# senzMate_ecandMoisture_design_cycle2.net
KiCad netlist of a schematic drawn in Altium Designer
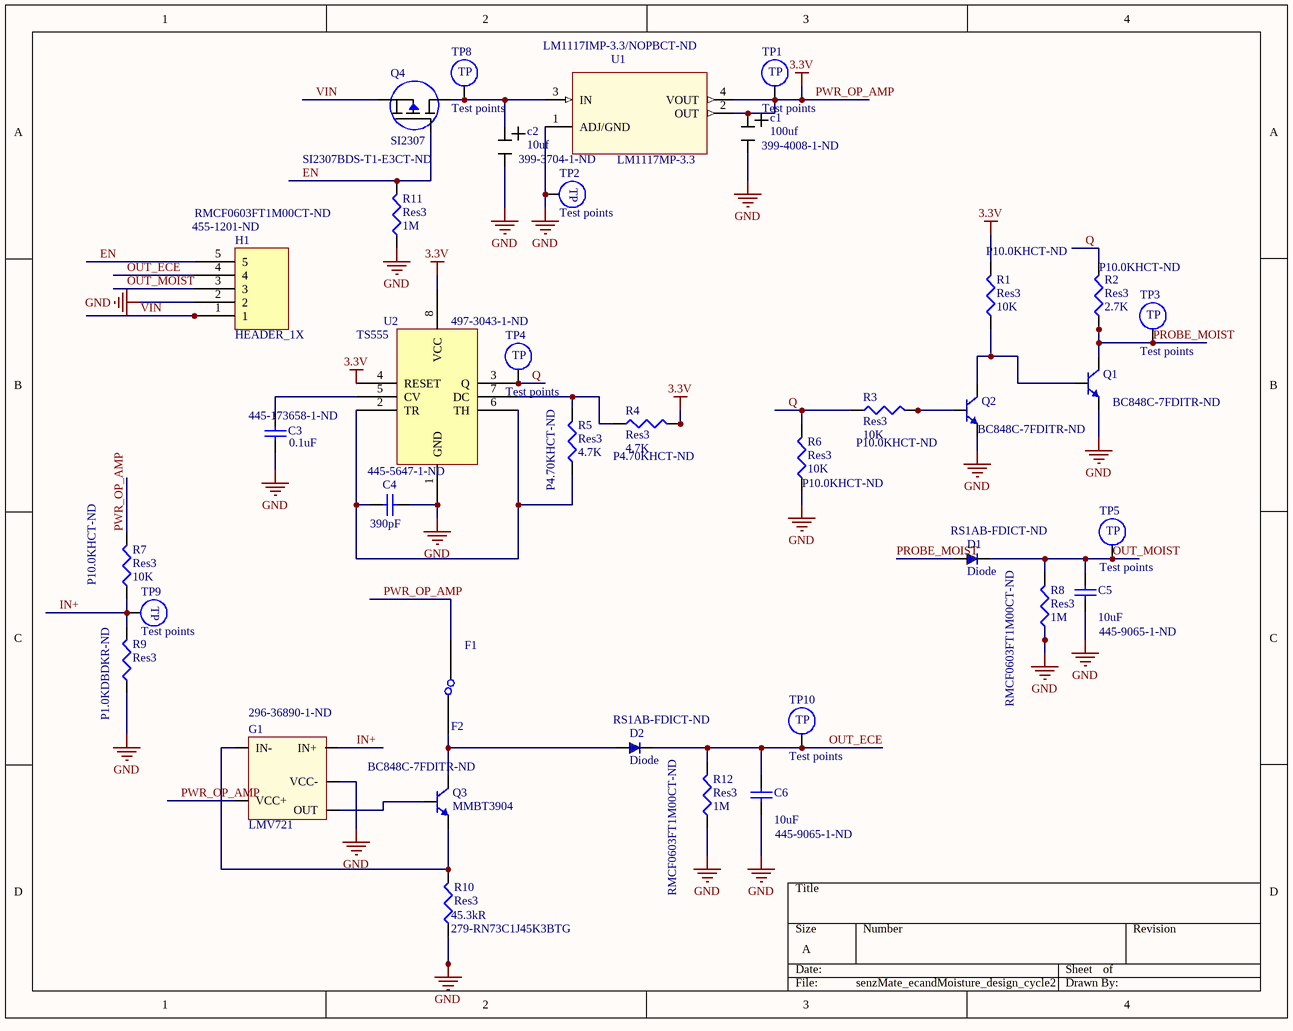
[diagram p0: senzMate_ecandMoisture_design_cycle2.SchDoc]

(export (version "E")
  (design (tool "Eeschema 10.0.6"))
  (components
    (comp (ref "c1")
      (value "100uf")
      (footprint "tan_cap")
      (description "Tantalum Surface Mount Capacitors – Standard Tantalum")
      (fields
        (field (name "SUPPLIER PART NUMBER 1") "399-4008-1-ND")
        (field (name "MANUFACTURER") "KEMET")
        (field (name "MANUFACTURER PART NUMBER") "T520B107M006ATE040")
      )
      (libsource (lib "Misc1") (part "tant_cap"))
    )
    (comp (ref "c2")
      (value "10uf")
      (footprint "tan_cap")
      (description "Tantalum Surface Mount Capacitors – Standard Tantalum")
      (fields
        (field (name "SUPPLIER PART NUMBER 1") "399-3704-1-ND")
        (field (name "MANUFACTURER") "KEMET")
        (field (name "MANUFACTURER PART NUMBER") "T491B106K006AT")
      )
      (libsource (lib "Misc1") (part "tant_cap"))
    )
    (comp (ref "C3")
      (value "0.1uF")
      (footprint "CAPACITOR_0603")
      (description "Capacitor")
      (fields
        (field (name "SUPPLIER PART NUMBER 1") "445-173658-1-ND")
        (field (name "MANUFACTURER") "TDK")
        (field (name "MANUFACTURER PART NUMBER") "CGA3E2X8R1E104K080AE")
        (field (name "PUBLISHER") "Altium Limited")
      )
      (libsource (lib "Miscellaneous Devices") (part "Cap"))
    )
    (comp (ref "C4")
      (value "390pF")
      (footprint "CAPACITOR_0603")
      (description "Capacitor")
      (fields
        (field (name "SUPPLIER PART NUMBER 1") "445-5647-1-ND")
        (field (name "MANUFACTURER") "TDK")
        (field (name "MANUFACTURER PART NUMBER") "CGA3E2C0G1H391J080AA")
        (field (name "PUBLISHER") "Altium Limited")
      )
      (libsource (lib "Miscellaneous Devices") (part "Cap"))
    )
    (comp (ref "C5")
      (value "10uF")
      (footprint "CAPACITOR_0603")
      (description "Capacitor")
      (fields
        (field (name "SUPPLIER PART NUMBER 1") "445-9065-1-ND")
        (field (name "MANUFACTURER") "TDK")
        (field (name "MANUFACTURER PART NUMBER") "C1608X5R1C106M080AB")
        (field (name "PUBLISHER") "Altium Limited")
      )
      (libsource (lib "Miscellaneous Devices") (part "Cap"))
    )
    (comp (ref "C6")
      (value "10uF")
      (footprint "CAPACITOR_0603")
      (description "Capacitor")
      (fields
        (field (name "SUPPLIER PART NUMBER 1") "445-9065-1-ND")
        (field (name "MANUFACTURER") "TDK")
        (field (name "MANUFACTURER PART NUMBER") "C1608X5R1C106M080AB")
        (field (name "PUBLISHER") "Altium Limited")
      )
      (libsource (lib "Miscellaneous Devices") (part "Cap"))
    )
    (comp (ref "D1")
      (value "Diode")
      (footprint "Diode")
      (fields
        (field (name "SUPPLIER PART NUMBER 1") "RS1AB-FDICT-ND")
        (field (name "MANUFACTURER") "Diodes")
        (field (name "MANUFACTURER PART NUMBER") "RS1AB-13-F")
      )
      (libsource (lib "Misc1") (part "Diode"))
    )
    (comp (ref "D2")
      (value "Diode")
      (footprint "Diode")
      (fields
        (field (name "SUPPLIER PART NUMBER 1") "RS1AB-FDICT-ND")
        (field (name "MANUFACTURER") "Diodes")
        (field (name "MANUFACTURER PART NUMBER") "RS1AB-13-F")
      )
      (libsource (lib "Misc1") (part "Diode"))
    )
    (comp (ref "F1") (value "Hole") (footprint "HOLE") (libsource (lib "Misc1") (part "Hole")))
    (comp (ref "F2") (value "Hole") (footprint "HOLE") (libsource (lib "Misc1") (part "Hole")))
    (comp (ref "G1")
      (value "LMV721")
      (footprint "lm721")
      (description "2.7V to 5V Comparator with Rail-to-Rail Output")
      (fields
        (field (name "SUPPLIER PART NUMBER 1") "296-36890-1-ND")
        (field (name "MANUFACTURER") "Texas Instruments")
        (field (name "MANUFACTURER PART NUMBER") "LMV721IDCKR")
      )
      (libsource (lib "Misc1") (part "lm721"))
    )
    (comp (ref "H1")
      (value "HEADER_1X")
      (footprint "CONNECTOR")
      (fields
        (field (name "SUPPLIER PART NUMBER 1") "455-1201-ND")
        (field (name "MANUFACTURER") "JST")
        (field (name "MANUFACTURER PART NUMBER") "ZHR-5")
      )
      (libsource (lib "Misc1") (part "HEADER1X5"))
    )
    (comp (ref "Q1")
      (value "~")
      (footprint "SOT95P245X110-3N")
      (description "Transistor npn")
      (fields
        (field (name "SUPPLIER PART NUMBER 1") "BC848C-7FDITR-ND")
        (field (name "MANUFACTURER") "Diodes")
        (field (name "MANUFACTURER PART NUMBER") "BC848C-7-F")
      )
      (libsource (lib "Misc1") (part "npn"))
    )
    (comp (ref "Q2")
      (value "~")
      (footprint "SOT95P245X110-3N")
      (description "Transistor npn")
      (fields
        (field (name "SUPPLIER PART NUMBER 1") "BC848C-7FDITR-ND")
        (field (name "MANUFACTURER") "Diodes")
        (field (name "MANUFACTURER PART NUMBER") "BC848C-7-F")
      )
      (libsource (lib "Misc1") (part "npn"))
    )
    (comp (ref "Q3")
      (value "MMBT3904")
      (footprint "SOT95P245X110-3N")
      (description "Transistor npn")
      (fields
        (field (name "SUPPLIER PART NUMBER 1") "BC848C-7FDITR-ND")
        (field (name "MANUFACTURER") "Diodes")
        (field (name "MANUFACTURER PART NUMBER") "BC848C-7-F")
      )
      (libsource (lib "Misc1") (part "npn"))
    )
    (comp (ref "Q4")
      (value "SI2307")
      (footprint "SI2307")
      (description "P-Channel 30-V (D-S) MOSFET")
      (fields
        (field (name "SUPPLIER PART NUMBER 1") "SI2307BDS-T1-E3CT-ND")
        (field (name "MANUFACTURER") "Vishay Siliconix")
        (field (name "MANUFACTURER PART NUMBER") "SI2307BDS-T1-E3")
      )
      (libsource (lib "Misc1") (part "SI2307"))
    )
    (comp (ref "R1")
      (value "Res3")
      (footprint "RES_0603")
      (description "Resistor")
      (fields
        (field (name "ALTIUM_VALUE") "10K")
        (field (name "SUPPLIER PART NUMBER 1") "P10.0KHCT-ND")
        (field (name "MANUFACTURER") "Panasonic")
        (field (name "MANUFACTURER PART NUMBER") "ERJ-3EKF1002V")
        (field (name "PUBLISHER") "Altium Limited")
      )
      (libsource (lib "Miscellaneous Devices") (part "Res3"))
    )
    (comp (ref "R2")
      (value "Res3")
      (footprint "RES_0603")
      (description "Resistor")
      (fields
        (field (name "ALTIUM_VALUE") "2.7K")
        (field (name "SUPPLIER PART NUMBER 1") "P10.0KHCT-ND")
        (field (name "MANUFACTURER") "Panasonic")
        (field (name "MANUFACTURER PART NUMBER") "ERJ-3EKF1002V")
        (field (name "PUBLISHER") "Altium Limited")
      )
      (libsource (lib "Miscellaneous Devices") (part "Res3"))
    )
    (comp (ref "R3")
      (value "Res3")
      (footprint "RES_0603")
      (description "Resistor")
      (fields
        (field (name "ALTIUM_VALUE") "10K")
        (field (name "SUPPLIER PART NUMBER 1") "P10.0KHCT-ND")
        (field (name "MANUFACTURER") "Panasonic")
        (field (name "MANUFACTURER PART NUMBER") "ERJ-3EKF1002V")
        (field (name "PUBLISHER") "Altium Limited")
      )
      (libsource (lib "Miscellaneous Devices") (part "Res3"))
    )
    (comp (ref "R4")
      (value "Res3")
      (footprint "RES_0603")
      (description "Resistor")
      (fields
        (field (name "ALTIUM_VALUE") "4.7K")
        (field (name "SUPPLIER PART NUMBER 1") "P4.70KHCT-ND")
        (field (name "MANUFACTURER") "Panasonic")
        (field (name "MANUFACTURER PART NUMBER") "ERJ-3EKF4701V")
        (field (name "PUBLISHER") "Altium Limited")
      )
      (libsource (lib "Miscellaneous Devices") (part "Res3"))
    )
    (comp (ref "R5")
      (value "Res3")
      (footprint "RES_0603")
      (description "Resistor")
      (fields
        (field (name "ALTIUM_VALUE") "4.7K")
        (field (name "SUPPLIER PART NUMBER 1") "P4.70KHCT-ND")
        (field (name "MANUFACTURER") "Panasonic")
        (field (name "MANUFACTURER PART NUMBER") "ERJ-3EKF4701V")
        (field (name "PUBLISHER") "Altium Limited")
      )
      (libsource (lib "Miscellaneous Devices") (part "Res3"))
    )
    (comp (ref "R6")
      (value "Res3")
      (footprint "RES_0603")
      (description "Resistor")
      (fields
        (field (name "ALTIUM_VALUE") "10K")
        (field (name "SUPPLIER PART NUMBER 1") "P10.0KHCT-ND")
        (field (name "MANUFACTURER") "Panasonic")
        (field (name "MANUFACTURER PART NUMBER") "ERJ-3EKF1002V")
        (field (name "PUBLISHER") "Altium Limited")
      )
      (libsource (lib "Miscellaneous Devices") (part "Res3"))
    )
    (comp (ref "R7")
      (value "Res3")
      (footprint "RES_0603")
      (description "Resistor")
      (fields
        (field (name "ALTIUM_VALUE") "10K")
        (field (name "SUPPLIER PART NUMBER 1") "P10.0KHCT-ND")
        (field (name "MANUFACTURER") "Panasonic")
        (field (name "MANUFACTURER PART NUMBER") "ERJ-3EKF1002V")
        (field (name "PUBLISHER") "Altium Limited")
      )
      (libsource (lib "Miscellaneous Devices") (part "Res3"))
    )
    (comp (ref "R8")
      (value "Res3")
      (footprint "RES_0603")
      (description "Resistor")
      (fields
        (field (name "ALTIUM_VALUE") "1M")
        (field (name "SUPPLIER PART NUMBER 1") "RMCF0603FT1M00CT-ND")
        (field (name "MANUFACTURER") "Stackpole Electronics")
        (field (name "MANUFACTURER PART NUMBER") "RMCF0603FT1M00")
        (field (name "PUBLISHER") "Altium Limited")
      )
      (libsource (lib "Miscellaneous Devices") (part "Res3"))
    )
    (comp (ref "R9")
      (value "Res3")
      (footprint "RES_0603")
      (description "Resistor")
      (fields
        (field (name "SUPPLIER PART NUMBER 1") "P1.0KDBDKR-ND")
        (field (name "MANUFACTURER") "Panasonic")
        (field (name "MANUFACTURER PART NUMBER") "ERA-3AEB102V")
      )
      (libsource (lib "Miscellaneous Devices") (part "Res3"))
    )
    (comp (ref "R10")
      (value "Res3")
      (footprint "RES_0603")
      (description "Resistor")
      (fields
        (field (name "SUPPLIER PART NUMBER 1") "279-RN73C1J45K3BTG")
        (field (name "MANUFACTURER") "TE Connectivity")
        (field (name "MANUFACTURER PART NUMBER") "RN73C1J45K3BTG")
        (field (name "RESISTANCE") "45.3kR")
      )
      (libsource (lib "Miscellaneous Devices") (part "Res3"))
    )
    (comp (ref "R11")
      (value "Res3")
      (footprint "RES_0603")
      (description "Resistor")
      (fields
        (field (name "ALTIUM_VALUE") "1M")
        (field (name "SUPPLIER PART NUMBER 1") "RMCF0603FT1M00CT-ND")
        (field (name "MANUFACTURER") "Stackpole Electronics")
        (field (name "MANUFACTURER PART NUMBER") "RMCF0603FT1M00")
        (field (name "PUBLISHER") "Altium Limited")
      )
      (libsource (lib "Miscellaneous Devices") (part "Res3"))
    )
    (comp (ref "R12")
      (value "Res3")
      (footprint "RES_0603")
      (description "Resistor")
      (fields
        (field (name "ALTIUM_VALUE") "1M")
        (field (name "SUPPLIER PART NUMBER 1") "RMCF0603FT1M00CT-ND")
        (field (name "MANUFACTURER") "Stackpole Electronics")
        (field (name "MANUFACTURER PART NUMBER") "RMCF0603FT1M00")
        (field (name "PUBLISHER") "Altium Limited")
      )
      (libsource (lib "Miscellaneous Devices") (part "Res3"))
    )
    (comp (ref "TP1") (value "Test points") (footprint "Test_point") (libsource (lib "Misc1") (part "TP")))
    (comp (ref "TP2") (value "Test points") (footprint "Test_point") (libsource (lib "Misc1") (part "TP")))
    (comp (ref "TP3") (value "Test points") (footprint "Test_point") (libsource (lib "Misc1") (part "TP")))
    (comp (ref "TP4") (value "Test points") (footprint "Test_point") (libsource (lib "Misc1") (part "TP")))
    (comp (ref "TP5") (value "Test points") (footprint "Test_point") (libsource (lib "Misc1") (part "TP")))
    (comp (ref "TP8") (value "Test points") (footprint "Test_point") (libsource (lib "Misc1") (part "TP")))
    (comp (ref "TP9") (value "Test points") (footprint "Test_point") (libsource (lib "Misc1") (part "TP")))
    (comp (ref "TP10") (value "Test points") (footprint "Test_point") (libsource (lib "Misc1") (part "TP")))
    (comp (ref "U1")
      (value "LM1117MP-3.3")
      (footprint "*SOT230P696X180-4N")
      (description "LDO Regulator Pos 3.3V 0.8A 4-Pin_3+Tab_ SOT-223 T/R")
      (fields
        (field (name "MF") "Texas Instruments")
        (field (name "SUPPLIER PART NUMBER 1") "LM1117IMP-3.3/NOPBCT-ND")
        (field (name "MANUFACTURER PART NUMBER") "LM1117IMP-3.3/NOPB")
      )
      (libsource (lib "LM1117MP-3.3") (part "LM1117MP-3.3"))
    )
    (comp (ref "U2")
      (value "TS555")
      (footprint "SOP127P600X175-8N")
      (description "Timer")
      (fields
        (field (name "SUPPLIER PART NUMBER 1") "497-3043-1-ND")
        (field (name "MANUFACTURER") "STMicroelectronics")
        (field (name "MANUFACTURER PART NUMBER") "TS555CD-T")
      )
      (libsource (lib "TI") (part "LM555"))
    )
  )
  (nets
    (net (code "1") (name "/EN") (class "Default")
      (node (ref "H1") (pin "5") (pinfunction "5_5") (pintype "passive"))
      (node (ref "Q4") (pin "1") (pinfunction "Gate_1") (pintype "passive"))
      (node (ref "R11") (pin "2") (pinfunction "2_2") (pintype "passive"))
    )
    (net (code "2") (name "/IN+") (class "Default")
      (node (ref "G1") (pin "3") (pinfunction "IN+_3") (pintype "passive"))
      (node (ref "R7") (pin "1") (pinfunction "1_1") (pintype "passive"))
      (node (ref "R9") (pin "2") (pinfunction "2_2") (pintype "passive"))
      (node (ref "TP9") (pin "1") (pinfunction "1_1") (pintype "passive"))
    )
    (net (code "3") (name "/OUT_ECE") (class "Default")
      (node (ref "C6") (pin "2") (pinfunction "2_2") (pintype "passive"))
      (node (ref "D2") (pin "2") (pinfunction "K_2") (pintype "passive"))
      (node (ref "H1") (pin "4") (pinfunction "4_4") (pintype "passive"))
      (node (ref "R12") (pin "2") (pinfunction "2_2") (pintype "passive"))
      (node (ref "TP10") (pin "1") (pinfunction "1_1") (pintype "passive"))
    )
    (net (code "4") (name "/OUT_MOIST") (class "Default")
      (node (ref "C5") (pin "2") (pinfunction "2_2") (pintype "passive"))
      (node (ref "D1") (pin "2") (pinfunction "K_2") (pintype "passive"))
      (node (ref "H1") (pin "3") (pinfunction "3_3") (pintype "passive"))
      (node (ref "R8") (pin "2") (pinfunction "2_2") (pintype "passive"))
      (node (ref "TP5") (pin "1") (pinfunction "1_1") (pintype "passive"))
    )
    (net (code "5") (name "/PROBE_MOIST") (class "Default")
      (node (ref "D1") (pin "1") (pinfunction "A_1") (pintype "passive"))
      (node (ref "Q1") (pin "3") (pinfunction "C_3") (pintype "passive"))
      (node (ref "R2") (pin "1") (pinfunction "1_1") (pintype "passive"))
      (node (ref "TP3") (pin "1") (pinfunction "1_1") (pintype "passive"))
    )
    (net (code "6") (name "/Q") (class "Default")
      (node (ref "R2") (pin "2") (pinfunction "2_2") (pintype "passive"))
      (node (ref "R3") (pin "1") (pinfunction "1_1") (pintype "passive"))
      (node (ref "R6") (pin "2") (pinfunction "2_2") (pintype "passive"))
      (node (ref "TP4") (pin "1") (pinfunction "1_1") (pintype "passive"))
      (node (ref "U2") (pin "3") (pinfunction "Q_3") (pintype "passive"))
    )
    (net (code "7") (name "/VIN") (class "Default")
      (node (ref "H1") (pin "1") (pinfunction "1_1") (pintype "passive"))
      (node (ref "Q4") (pin "2") (pinfunction "Source_2") (pintype "passive"))
    )
    (net (code "8") (name "3.3V") (class "Default")
      (node (ref "F1") (pin "1") (pinfunction "1_1") (pintype "passive"))
      (node (ref "G1") (pin "5") (pinfunction "VCC+_5") (pintype "passive"))
      (node (ref "R1") (pin "2") (pinfunction "2_2") (pintype "passive"))
      (node (ref "R4") (pin "2") (pinfunction "2_2") (pintype "passive"))
      (node (ref "R7") (pin "2") (pinfunction "2_2") (pintype "passive"))
      (node (ref "TP1") (pin "1") (pinfunction "1_1") (pintype "passive"))
      (node (ref "U1") (pin "2") (pinfunction "OUT_2") (pintype "output"))
      (node (ref "U1") (pin "4") (pinfunction "VOUT_4") (pintype "output"))
      (node (ref "U2") (pin "4") (pinfunction "RESET_4") (pintype "passive"))
      (node (ref "U2") (pin "8") (pinfunction "VCC_8") (pintype "passive"))
      (node (ref "c1") (pin "1") (pinfunction "1_1") (pintype "passive"))
    )
    (net (code "9") (name "GND") (class "Default")
      (node (ref "C3") (pin "1") (pinfunction "1_1") (pintype "passive"))
      (node (ref "C4") (pin "1") (pinfunction "1_1") (pintype "passive"))
      (node (ref "C5") (pin "1") (pinfunction "1_1") (pintype "passive"))
      (node (ref "C6") (pin "1") (pinfunction "1_1") (pintype "passive"))
      (node (ref "G1") (pin "2") (pinfunction "VCC-_2") (pintype "passive"))
      (node (ref "H1") (pin "2") (pinfunction "2_2") (pintype "passive"))
      (node (ref "Q1") (pin "1") (pinfunction "E_1") (pintype "passive"))
      (node (ref "Q2") (pin "1") (pinfunction "E_1") (pintype "passive"))
      (node (ref "R10") (pin "1") (pinfunction "1_1") (pintype "passive"))
      (node (ref "R11") (pin "1") (pinfunction "1_1") (pintype "passive"))
      (node (ref "R12") (pin "1") (pinfunction "1_1") (pintype "passive"))
      (node (ref "R6") (pin "1") (pinfunction "1_1") (pintype "passive"))
      (node (ref "R8") (pin "1") (pinfunction "1_1") (pintype "passive"))
      (node (ref "R9") (pin "1") (pinfunction "1_1") (pintype "passive"))
      (node (ref "TP2") (pin "1") (pinfunction "1_1") (pintype "passive"))
      (node (ref "U1") (pin "1") (pinfunction "ADJ/GND_1") (pintype "passive"))
      (node (ref "U2") (pin "1") (pinfunction "GND_1") (pintype "passive"))
      (node (ref "c1") (pin "2") (pinfunction "2_2") (pintype "passive"))
      (node (ref "c2") (pin "2") (pinfunction "2_2") (pintype "passive"))
    )
    (net (code "10") (name "Net-(D2-A)") (class "Default")
      (node (ref "D2") (pin "1") (pinfunction "A_1") (pintype "passive"))
      (node (ref "F2") (pin "1") (pinfunction "1_1") (pintype "passive"))
      (node (ref "Q3") (pin "3") (pinfunction "C_3") (pintype "passive"))
    )
    (net (code "11") (name "Net-(G1-IN-)") (class "Default")
      (node (ref "G1") (pin "4") (pinfunction "IN-_4") (pintype "passive"))
      (node (ref "Q3") (pin "1") (pinfunction "E_1") (pintype "passive"))
      (node (ref "R10") (pin "2") (pinfunction "2_2") (pintype "passive"))
    )
    (net (code "12") (name "Net-(G1-OUT)") (class "Default")
      (node (ref "G1") (pin "1") (pinfunction "OUT_1") (pintype "passive"))
      (node (ref "Q3") (pin "2") (pinfunction "B_2") (pintype "passive"))
    )
    (net (code "13") (name "Net-(Q1-B)") (class "Default")
      (node (ref "Q1") (pin "2") (pinfunction "B_2") (pintype "passive"))
      (node (ref "Q2") (pin "3") (pinfunction "C_3") (pintype "passive"))
      (node (ref "R1") (pin "1") (pinfunction "1_1") (pintype "passive"))
    )
    (net (code "14") (name "Net-(Q2-B)") (class "Default")
      (node (ref "Q2") (pin "2") (pinfunction "B_2") (pintype "passive"))
      (node (ref "R3") (pin "2") (pinfunction "2_2") (pintype "passive"))
    )
    (net (code "15") (name "Net-(Q4-Drain)") (class "Default")
      (node (ref "Q4") (pin "3") (pinfunction "Drain_3") (pintype "passive"))
      (node (ref "TP8") (pin "1") (pinfunction "1_1") (pintype "passive"))
      (node (ref "U1") (pin "3") (pinfunction "IN_3") (pintype "input"))
      (node (ref "c2") (pin "1") (pinfunction "1_1") (pintype "passive"))
    )
    (net (code "16") (name "Net-(U2-CV)") (class "Default")
      (node (ref "C3") (pin "2") (pinfunction "2_2") (pintype "passive"))
      (node (ref "U2") (pin "5") (pinfunction "CV_5") (pintype "passive"))
    )
    (net (code "17") (name "Net-(U2-DC)") (class "Default")
      (node (ref "R4") (pin "1") (pinfunction "1_1") (pintype "passive"))
      (node (ref "R5") (pin "2") (pinfunction "2_2") (pintype "passive"))
      (node (ref "U2") (pin "7") (pinfunction "DC_7") (pintype "passive"))
    )
    (net (code "18") (name "Net-(U2-TH)") (class "Default")
      (node (ref "C4") (pin "2") (pinfunction "2_2") (pintype "passive"))
      (node (ref "R5") (pin "1") (pinfunction "1_1") (pintype "passive"))
      (node (ref "U2") (pin "2") (pinfunction "TR_2") (pintype "passive"))
      (node (ref "U2") (pin "6") (pinfunction "TH_6") (pintype "passive"))
    )
  )
)
